# Devices.net
KiCad netlist of a schematic drawn in Altium Designer
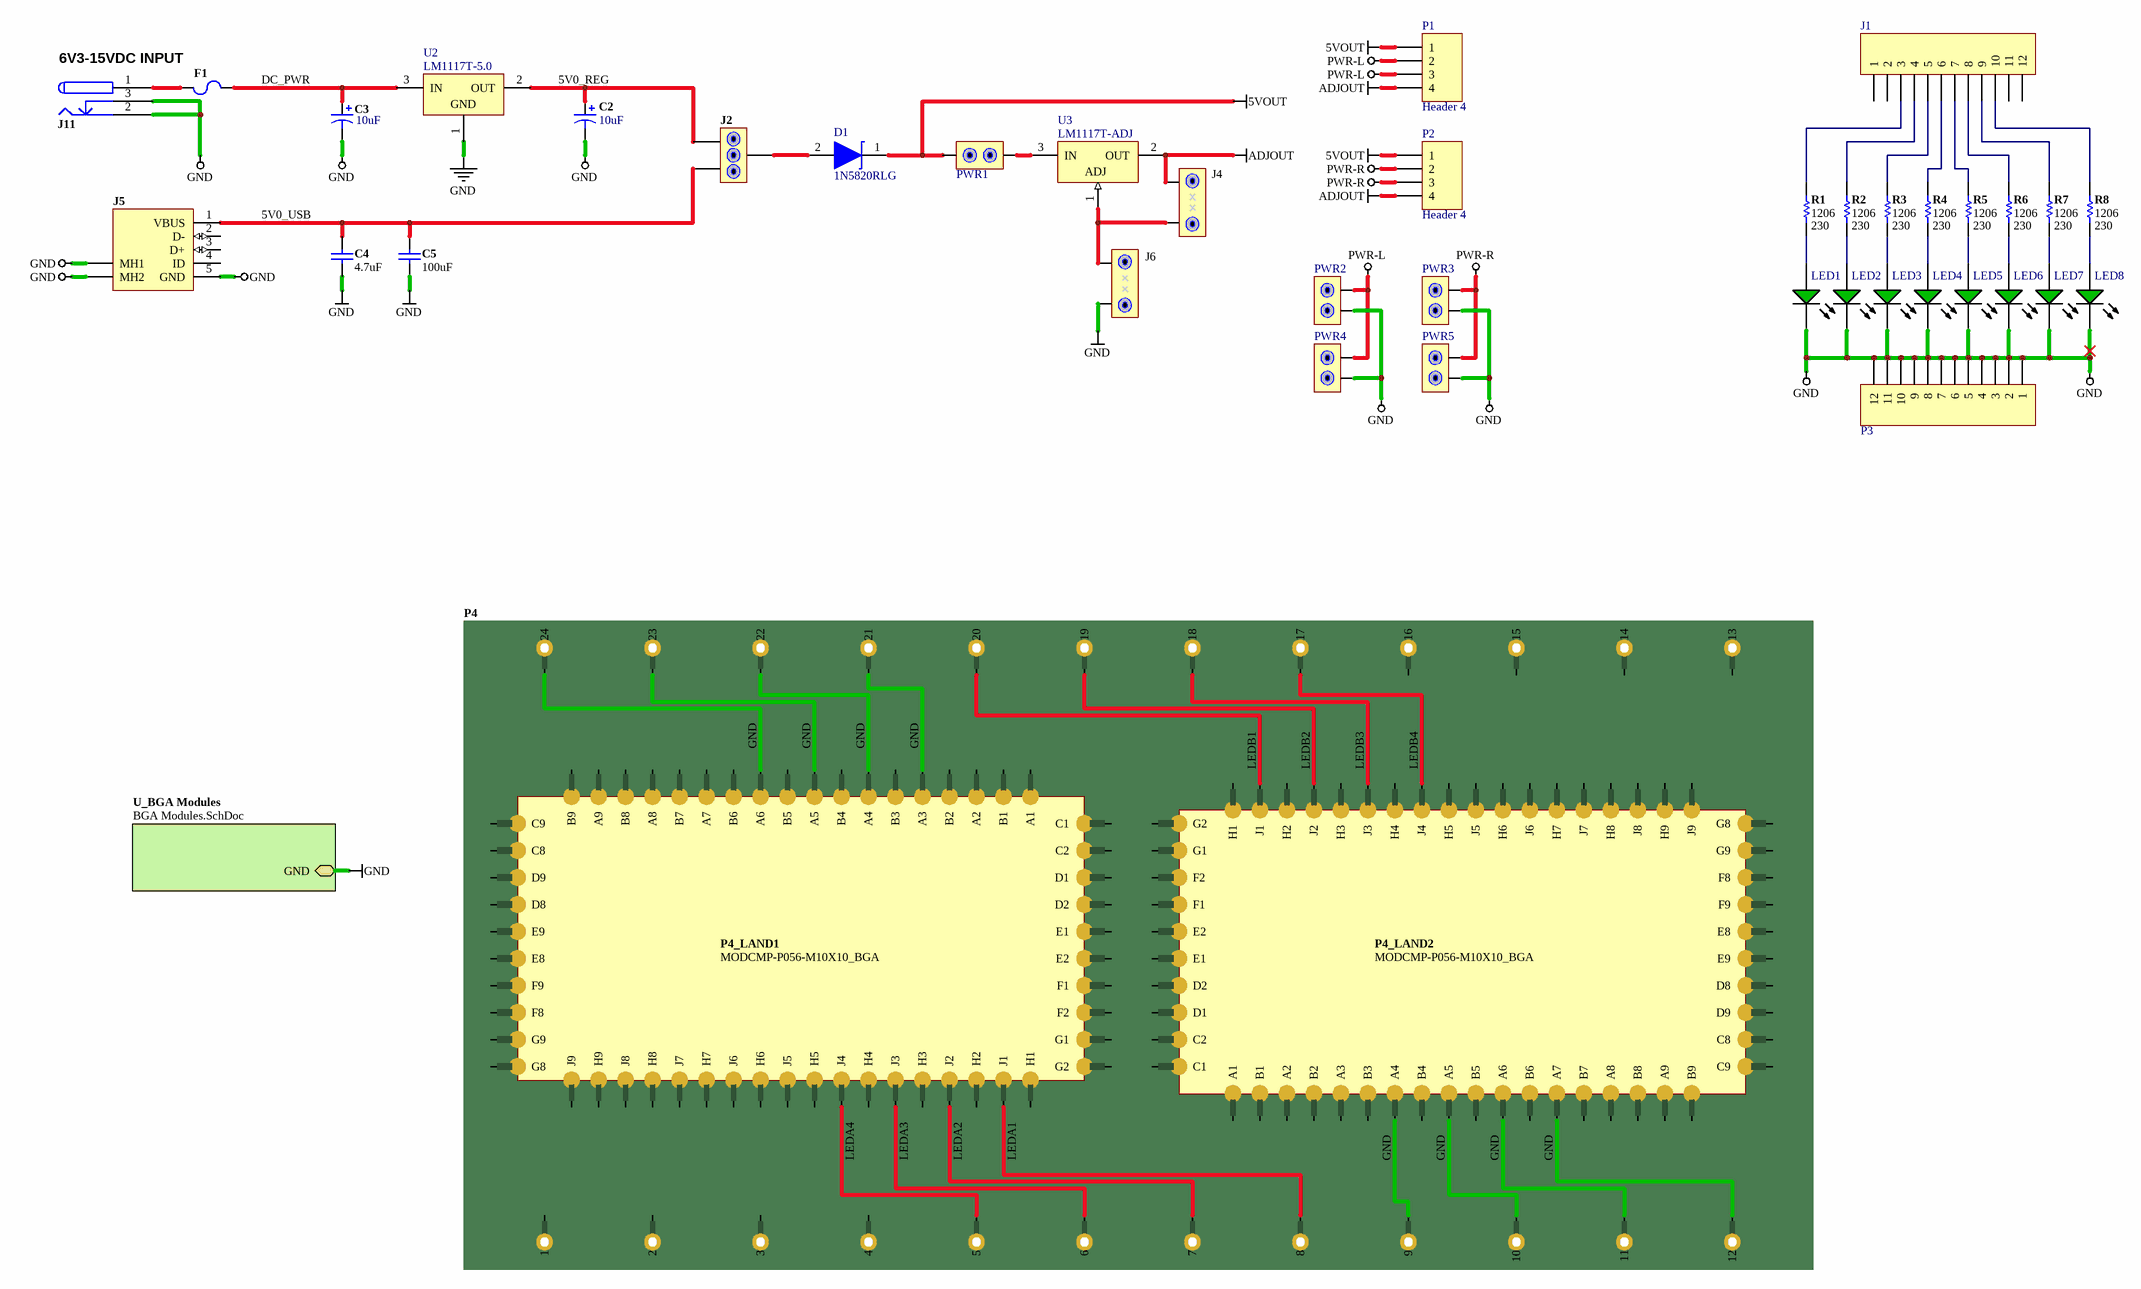
[diagram p0: Devices.SchDoc]

(export (version "E")
  (design (tool "Eeschema 10.0.6"))
  (components
    (comp (ref "C2")
      (value "TAJB106K020R")
      (footprint "AVX-CAPC3528_V")
      (description "Capacitor, Tantalum, 10uF 10% 20V MCCT-B (3528)")
      (fields
        (field (name "CAPACITANCE") "10uF")
        (field (name "MANUFACTURER") "AVX")
        (field (name "TOLERANCE") "10%")
      )
      (libsource (lib "Altium Content Vault") (part "CMP-0279-00001-1"))
    )
    (comp (ref "C3")
      (value "TAJB106K020R")
      (footprint "AVX-CAPC3528_V")
      (description "Capacitor, Tantalum, 10uF 10% 20V MCCT-B (3528)")
      (fields
        (field (name "CAPACITANCE") "10uF")
        (field (name "MANUFACTURER") "AVX")
        (field (name "TOLERANCE") "10%")
      )
      (libsource (lib "Altium Content Vault") (part "CMP-0279-00001-1"))
    )
    (comp (ref "C4")
      (value "4.7uF")
      (footprint "CAPC1206(3216)190_L")
      (description "CAP 100uF 6.3V ?0% 1206 (3216 Metric) Thickness 1.9mm SMD")
      (fields (field (name "TOLERANCE") "?0%") (field (name "Comment") "AP 4.7uF 6.3V 1206(3216)"))
      (libsource (lib "Component_DB") (part "CAP_NP"))
    )
    (comp (ref "C5")
      (value "100uF")
      (footprint "CAPC1206(3216)190_L")
      (description "CAP 100uF 6.3V ?0% 1206 (3216 Metric) Thickness 1.9mm SMD")
      (fields (field (name "TOLERANCE") "?0%") (field (name "Comment") "AP 100uF 6.3V 1206(3216)"))
      (libsource (lib "Component_DB") (part "CAP_NP"))
    )
    (comp (ref "D1")
      (value "1N5820RLG")
      (footprint "ONSC-AXIAL_LEAD-2-267-05_V")
      (description "Rectifier, 2-Pin Axial_Lead, Pb-Free, Tape and Reel")
      (fields (field (name "MANUFACTURER") "On Semiconductor"))
      (libsource (lib "Soldering_Trainer_Prj (backup)") (part "CMP-1055-00027-1"))
    )
    (comp (ref "F1")
      (value "SMD2920P300TF")
      (footprint "FUSE2920")
      (description "PTC RESETTABLE 16V 3A SMD 2920")
      (libsource (lib "Component_DB") (part "FUSE-2"))
    )
    (comp (ref "J1")
      (value "Header 12")
      (footprint "HDR1X12")
      (description "Header, 12-Pin")
      (fields (field (name "PUBLISHER") "Altium Limited"))
      (libsource (lib "") (part "Header 12_1"))
    )
    (comp (ref "J2")
      (value "3-WAY JUMPER")
      (footprint "HDR1X3")
      (description "3-Way Jumper - Center Output")
      (fields (field (name "MANUFACTURER PART NUMBER") "71417-103HLF"))
      (libsource (lib "3-WAY JUMPER") (part "3-WAY JUMPER"))
    )
    (comp (ref "J4")
      (value "801-87-004-10-001101")
      (footprint "HDR1X4")
      (description "IC REG LDO 3V3 .3A SOT25")
      (fields (field (name "DIGIKEY PART NUMBER") "1212-1181-ND"))
      (libsource (lib "801-87-004-10-001101 Socket") (part "801-87-004-10-001101"))
    )
    (comp (ref "J5")
      (value "UX60SC-MB-5S8")
      (footprint "UX60SC-MB-5S8")
      (description "CONN RCPT MINI USB2.0 5POS SLD")
      (libsource (lib "Component_DB") (part "UX60SC-MB-5S8"))
    )
    (comp (ref "J6")
      (value "801-87-004-10-001101")
      (footprint "HDR1X4")
      (description "IC REG LDO 3V3 .3A SOT25")
      (fields (field (name "DIGIKEY PART NUMBER") "1212-1181-ND"))
      (libsource (lib "801-87-004-10-001101 Socket") (part "801-87-004-10-001101"))
    )
    (comp (ref "J11")
      (value "PWR CONNECTOR")
      (footprint "PJ-102AH")
      (description "Connector, 3 Conductor Power Jack")
      (fields (field (name "MANUFACTURER PART NUMBER") "CP-102AH-ND"))
      (libsource (lib "PWR_CONNECTOR_3") (part "POWER-CONNECTOR-3"))
    )
    (comp (ref "LED1")
      (value "LED_1206")
      (footprint "RESC1206(3216)75_L")
      (description "GREEN color, 1206, SMD")
      (libsource (lib "Component_DB") (part "LED_GREEN_A1K2-2.A1"))
    )
    (comp (ref "LED2")
      (value "LED_1206")
      (footprint "RESC1206(3216)75_L")
      (description "GREEN color, 1206, SMD")
      (libsource (lib "Component_DB") (part "LED_GREEN_A1K2-2.A1"))
    )
    (comp (ref "LED3")
      (value "LED_1206")
      (footprint "RESC1206(3216)75_L")
      (description "GREEN color, 1206, SMD")
      (libsource (lib "Component_DB") (part "LED_GREEN_A1K2-2.A1"))
    )
    (comp (ref "LED4")
      (value "LED_1206")
      (footprint "RESC1206(3216)75_L")
      (description "GREEN color, 1206, SMD")
      (libsource (lib "Component_DB") (part "LED_GREEN_A1K2-2.A1"))
    )
    (comp (ref "LED5")
      (value "LED_1206")
      (footprint "RESC1206(3216)75_L")
      (description "GREEN color, 1206, SMD")
      (libsource (lib "Component_DB") (part "LED_GREEN_A1K2-2.A1"))
    )
    (comp (ref "LED6")
      (value "LED_1206")
      (footprint "RESC1206(3216)75_L")
      (description "GREEN color, 1206, SMD")
      (libsource (lib "Component_DB") (part "LED_GREEN_A1K2-2.A1"))
    )
    (comp (ref "LED7")
      (value "LED_1206")
      (footprint "RESC1206(3216)75_L")
      (description "GREEN color, 1206, SMD")
      (libsource (lib "Component_DB") (part "LED_GREEN_A1K2-2.A1"))
    )
    (comp (ref "LED8")
      (value "LED_1206")
      (footprint "RESC1206(3216)75_L")
      (description "GREEN color, 1206, SMD")
      (libsource (lib "Component_DB") (part "LED_GREEN_A1K2-2.A1"))
    )
    (comp (ref "P1")
      (value "Header 4")
      (footprint "HDR1X4")
      (description "Header, 4-Pin")
      (fields (field (name "PUBLISHER") "Altium Limited"))
      (libsource (lib "Miscellaneous Connectors") (part "Header 4"))
    )
    (comp (ref "P2")
      (value "Header 4")
      (footprint "HDR1X4")
      (description "Header, 4-Pin")
      (fields (field (name "PUBLISHER") "Altium Limited"))
      (libsource (lib "Miscellaneous Connectors") (part "Header 4"))
    )
    (comp (ref "P3")
      (value "Header 12")
      (footprint "HDR1X12")
      (description "Header, 12-Pin")
      (fields (field (name "PUBLISHER") "Altium Limited"))
      (libsource (lib "Miscellaneous Connectors") (part "Header 12"))
    )
    (comp (ref "P4")
      (value "BBCMP-P24-M1200X700")
      (footprint "BBCMP-P24-M1200X700")
      (libsource (lib "MODCMP-P056-M10X10_BGA") (part "BBCMP-P24"))
    )
    (comp (ref "P4_LAND1")
      (value "MODCMP-P056-M10X10_BGA")
      (footprint "MB2100.01.A.2")
      (description "Module Component - 1mm Pitch, 56-Pin, 10mmX10mm")
      (libsource (lib "MODCMP-P056-M10X10_BGA") (part "MODCMP-P056-M10X10_BGA"))
    )
    (comp (ref "P4_LAND2")
      (value "MODCMP-P056-M10X10_BGA")
      (footprint "MB2100.01.A.2")
      (description "Module Component - 1mm Pitch, 56-Pin, 10mmX10mm")
      (libsource (lib "MODCMP-P056-M10X10_BGA") (part "MODCMP-P056-M10X10_BGA"))
    )
    (comp (ref "PWR1")
      (value "Jumper")
      (footprint "JMP1X2")
      (description "Standard 2 Pin Jumper, 100mil spacing")
      (fields (field (name "MANUFACTURER PART NUMBER") "M20-9770246"))
      (libsource (lib "Soldering_Trainer_Prj") (part "JMP1X2_SERIES"))
    )
    (comp (ref "PWR2")
      (value "Jumper")
      (footprint "JMP1X2")
      (description "Standard 2 Pin Jumper, 100mil spacing")
      (fields (field (name "MANUFACTURER PART NUMBER") "M20-9770246"))
      (libsource (lib "JMP1X2") (part "JMP1X2"))
    )
    (comp (ref "PWR3")
      (value "Jumper")
      (footprint "JMP1X2")
      (description "Standard 2 Pin Jumper, 100mil spacing")
      (fields (field (name "MANUFACTURER PART NUMBER") "M20-9770246"))
      (libsource (lib "JMP1X2") (part "JMP1X2"))
    )
    (comp (ref "PWR4")
      (value "Jumper")
      (footprint "JMP1X2")
      (description "Standard 2 Pin Jumper, 100mil spacing")
      (fields (field (name "MANUFACTURER PART NUMBER") "M20-9770246"))
      (libsource (lib "JMP1X2") (part "JMP1X2"))
    )
    (comp (ref "PWR5")
      (value "Jumper")
      (footprint "JMP1X2")
      (description "Standard 2 Pin Jumper, 100mil spacing")
      (fields (field (name "MANUFACTURER PART NUMBER") "M20-9770246"))
      (libsource (lib "JMP1X2") (part "JMP1X2"))
    )
    (comp (ref "R1")
      (value "1206")
      (footprint "RESC1206(3216)75_L")
      (description "Jumper 0805 (2012 Metric)")
      (fields (field (name "VALUE (OHMS)") "230") (field (name "POWER") "None"))
      (libsource (lib "Component_DB") (part "RES"))
    )
    (comp (ref "R2")
      (value "1206")
      (footprint "RESC1206(3216)75_L")
      (description "Jumper 0805 (2012 Metric)")
      (fields (field (name "VALUE (OHMS)") "230") (field (name "POWER") "None"))
      (libsource (lib "Component_DB") (part "RES"))
    )
    (comp (ref "R3")
      (value "1206")
      (footprint "RESC1206(3216)75_L")
      (description "Jumper 0805 (2012 Metric)")
      (fields (field (name "VALUE (OHMS)") "230") (field (name "POWER") "None"))
      (libsource (lib "Component_DB") (part "RES"))
    )
    (comp (ref "R4")
      (value "1206")
      (footprint "RESC1206(3216)75_L")
      (description "Jumper 0805 (2012 Metric)")
      (fields (field (name "VALUE (OHMS)") "230") (field (name "POWER") "None"))
      (libsource (lib "Component_DB") (part "RES"))
    )
    (comp (ref "R5")
      (value "1206")
      (footprint "RESC1206(3216)75_L")
      (description "Jumper 0805 (2012 Metric)")
      (fields (field (name "VALUE (OHMS)") "230") (field (name "POWER") "None"))
      (libsource (lib "Component_DB") (part "RES"))
    )
    (comp (ref "R6")
      (value "1206")
      (footprint "RESC1206(3216)75_L")
      (description "Jumper 0805 (2012 Metric)")
      (fields (field (name "VALUE (OHMS)") "230") (field (name "POWER") "None"))
      (libsource (lib "Component_DB") (part "RES"))
    )
    (comp (ref "R7")
      (value "1206")
      (footprint "RESC1206(3216)75_L")
      (description "Jumper 0805 (2012 Metric)")
      (fields (field (name "VALUE (OHMS)") "230") (field (name "POWER") "None"))
      (libsource (lib "Component_DB") (part "RES"))
    )
    (comp (ref "R8")
      (value "1206")
      (footprint "RESC1206(3216)75_L")
      (description "Jumper 0805 (2012 Metric)")
      (fields (field (name "VALUE (OHMS)") "230") (field (name "POWER") "None"))
      (libsource (lib "Component_DB") (part "RES"))
    )
    (comp (ref "U2")
      (value "LM1117T-5.0")
      (footprint "T03B")
      (description "800mA Low-Dropout Linear Regulator, 3-pin TO-220")
      (fields (field (name "MANUFACTURER") "National Semiconductor"))
      (libsource (lib "Altium Content Vault") (part "PM-REG-LM1086-SIL3"))
    )
    (comp (ref "U3")
      (value "LM1117T-ADJ")
      (footprint "T03B")
      (description "800mA Low-Dropout Linear Regulator, 3-pin TO-220, Pb-Free")
      (fields (field (name "MANUFACTURER") "National Semiconductor"))
      (libsource (lib "Altium Content Vault") (part "CMP-0062-02492-2"))
    )
  )
  (nets
    (net (code "1") (name "/5V0_REG") (class "Default")
      (node (ref "C2") (pin "1") (pinfunction "1_1") (pintype "passive"))
      (node (ref "J2") (pin "1") (pinfunction "1_1") (pintype "passive"))
      (node (ref "U2") (pin "2") (pinfunction "OUT_2") (pintype "power_in"))
    )
    (net (code "2") (name "/5V0_USB") (class "Default")
      (node (ref "C4") (pin "1") (pinfunction "1_1") (pintype "passive"))
      (node (ref "C5") (pin "1") (pinfunction "1_1") (pintype "passive"))
      (node (ref "J2") (pin "3") (pinfunction "3_3") (pintype "passive"))
      (node (ref "J5") (pin "1") (pinfunction "VBUS_1") (pintype "power_in"))
    )
    (net (code "3") (name "/DC_PWR") (class "Default")
      (node (ref "C3") (pin "1") (pinfunction "1_1") (pintype "passive"))
      (node (ref "F1") (pin "1") (pinfunction "1_1") (pintype "passive"))
      (node (ref "U2") (pin "3") (pinfunction "IN_3") (pintype "power_in"))
    )
    (net (code "4") (name "/LEDA1") (class "Default")
      (node (ref "P4") (pin "8") (pinfunction "8_8") (pintype "passive"))
      (node (ref "P4_LAND1") (pin "J1") (pinfunction "J1_J1") (pintype "passive"))
    )
    (net (code "5") (name "/LEDA2") (class "Default")
      (node (ref "P4") (pin "7") (pinfunction "7_7") (pintype "passive"))
      (node (ref "P4_LAND1") (pin "J2") (pinfunction "J2_J2") (pintype "passive"))
    )
    (net (code "6") (name "/LEDA3") (class "Default")
      (node (ref "P4") (pin "6") (pinfunction "6_6") (pintype "passive"))
      (node (ref "P4_LAND1") (pin "J3") (pinfunction "J3_J3") (pintype "passive"))
    )
    (net (code "7") (name "/LEDA4") (class "Default")
      (node (ref "P4") (pin "5") (pinfunction "5_5") (pintype "passive"))
      (node (ref "P4_LAND1") (pin "J4") (pinfunction "J4_J4") (pintype "passive"))
    )
    (net (code "8") (name "/LEDB1") (class "Default")
      (node (ref "P4") (pin "20") (pinfunction "20_20") (pintype "passive"))
      (node (ref "P4_LAND2") (pin "J1") (pinfunction "J1_J1") (pintype "passive"))
    )
    (net (code "9") (name "/LEDB2") (class "Default")
      (node (ref "P4") (pin "19") (pinfunction "19_19") (pintype "passive"))
      (node (ref "P4_LAND2") (pin "J2") (pinfunction "J2_J2") (pintype "passive"))
    )
    (net (code "10") (name "/LEDB3") (class "Default")
      (node (ref "P4") (pin "18") (pinfunction "18_18") (pintype "passive"))
      (node (ref "P4_LAND2") (pin "J3") (pinfunction "J3_J3") (pintype "passive"))
    )
    (net (code "11") (name "/LEDB4") (class "Default")
      (node (ref "P4") (pin "17") (pinfunction "17_17") (pintype "passive"))
      (node (ref "P4_LAND2") (pin "J4") (pinfunction "J4_J4") (pintype "passive"))
    )
    (net (code "12") (name "5VOUT") (class "Default")
      (node (ref "D1") (pin "1") (pinfunction "K_1") (pintype "passive"))
      (node (ref "P1") (pin "1") (pinfunction "1_1") (pintype "passive"))
      (node (ref "P2") (pin "1") (pinfunction "1_1") (pintype "passive"))
      (node (ref "PWR1") (pin "1") (pinfunction "1_1") (pintype "passive"))
    )
    (net (code "13") (name "ADJOUT") (class "Default")
      (node (ref "J4") (pin "1") (pinfunction "1_1") (pintype "passive"))
      (node (ref "P1") (pin "4") (pinfunction "4_4") (pintype "passive"))
      (node (ref "P2") (pin "4") (pinfunction "4_4") (pintype "passive"))
      (node (ref "U3") (pin "2") (pinfunction "OUT_2") (pintype "power_in"))
    )
    (net (code "14") (name "GND") (class "Default")
      (node (ref "C2") (pin "2") (pinfunction "2_2") (pintype "passive"))
      (node (ref "C3") (pin "2") (pinfunction "2_2") (pintype "passive"))
      (node (ref "C4") (pin "2") (pinfunction "2_2") (pintype "passive"))
      (node (ref "C5") (pin "2") (pinfunction "2_2") (pintype "passive"))
      (node (ref "J11") (pin "2") (pintype "power_in"))
      (node (ref "J11") (pin "3") (pintype "power_in"))
      (node (ref "J5") (pin "5") (pinfunction "GND_5") (pintype "power_in"))
      (node (ref "J5") (pin "MH1") (pinfunction "MH1_MH1") (pintype "passive"))
      (node (ref "J5") (pin "MH2") (pinfunction "MH2_MH2") (pintype "passive"))
      (node (ref "J6") (pin "4") (pinfunction "4_4") (pintype "passive"))
      (node (ref "LED1") (pin "2") (pinfunction "K_2") (pintype "passive"))
      (node (ref "LED2") (pin "2") (pinfunction "K_2") (pintype "passive"))
      (node (ref "LED3") (pin "2") (pinfunction "K_2") (pintype "passive"))
      (node (ref "LED4") (pin "2") (pinfunction "K_2") (pintype "passive"))
      (node (ref "LED5") (pin "2") (pinfunction "K_2") (pintype "passive"))
      (node (ref "LED6") (pin "2") (pinfunction "K_2") (pintype "passive"))
      (node (ref "LED7") (pin "2") (pinfunction "K_2") (pintype "passive"))
      (node (ref "LED8") (pin "2") (pinfunction "K_2") (pintype "passive"))
      (node (ref "P3") (pin "1") (pinfunction "1_1") (pintype "passive"))
      (node (ref "P3") (pin "10") (pinfunction "10_10") (pintype "passive"))
      (node (ref "P3") (pin "11") (pinfunction "11_11") (pintype "passive"))
      (node (ref "P3") (pin "12") (pinfunction "12_12") (pintype "passive"))
      (node (ref "P3") (pin "2") (pinfunction "2_2") (pintype "passive"))
      (node (ref "P3") (pin "3") (pinfunction "3_3") (pintype "passive"))
      (node (ref "P3") (pin "4") (pinfunction "4_4") (pintype "passive"))
      (node (ref "P3") (pin "5") (pinfunction "5_5") (pintype "passive"))
      (node (ref "P3") (pin "6") (pinfunction "6_6") (pintype "passive"))
      (node (ref "P3") (pin "7") (pinfunction "7_7") (pintype "passive"))
      (node (ref "P3") (pin "8") (pinfunction "8_8") (pintype "passive"))
      (node (ref "P3") (pin "9") (pinfunction "9_9") (pintype "passive"))
      (node (ref "P4") (pin "10") (pinfunction "10_10") (pintype "passive"))
      (node (ref "P4") (pin "11") (pinfunction "11_11") (pintype "passive"))
      (node (ref "P4") (pin "12") (pinfunction "12_12") (pintype "passive"))
      (node (ref "P4") (pin "21") (pinfunction "21_21") (pintype "passive"))
      (node (ref "P4") (pin "22") (pinfunction "22_22") (pintype "passive"))
      (node (ref "P4") (pin "23") (pinfunction "23_23") (pintype "passive"))
      (node (ref "P4") (pin "24") (pinfunction "24_24") (pintype "passive"))
      (node (ref "P4") (pin "9") (pinfunction "9_9") (pintype "passive"))
      (node (ref "P4_LAND1") (pin "A3") (pinfunction "A3_A3") (pintype "passive"))
      (node (ref "P4_LAND1") (pin "A4") (pinfunction "A4_A4") (pintype "passive"))
      (node (ref "P4_LAND1") (pin "A5") (pinfunction "A5_A5") (pintype "passive"))
      (node (ref "P4_LAND1") (pin "A6") (pinfunction "A6_A6") (pintype "passive"))
      (node (ref "P4_LAND2") (pin "A4") (pinfunction "A4_A4") (pintype "passive"))
      (node (ref "P4_LAND2") (pin "A5") (pinfunction "A5_A5") (pintype "passive"))
      (node (ref "P4_LAND2") (pin "A6") (pinfunction "A6_A6") (pintype "passive"))
      (node (ref "P4_LAND2") (pin "A7") (pinfunction "A7_A7") (pintype "passive"))
      (node (ref "PWR2") (pin "1") (pinfunction "1_1") (pintype "passive"))
      (node (ref "PWR3") (pin "1") (pinfunction "1_1") (pintype "passive"))
      (node (ref "PWR4") (pin "1") (pinfunction "1_1") (pintype "passive"))
      (node (ref "PWR5") (pin "1") (pinfunction "1_1") (pintype "passive"))
      (node (ref "U2") (pin "1") (pinfunction "GND_1") (pintype "power_in"))
    )
    (net (code "15") (name "Net-(D1-A)") (class "Default")
      (node (ref "D1") (pin "2") (pinfunction "A_2") (pintype "passive"))
      (node (ref "J2") (pin "2") (pinfunction "2_2") (pintype "passive"))
    )
    (net (code "16") (name "Net-(F1-Pad2)") (class "Default")
      (node (ref "F1") (pin "2") (pinfunction "2_2") (pintype "passive"))
      (node (ref "J11") (pin "1") (pintype "power_in"))
    )
    (net (code "17") (name "Net-(J1-Pad3)") (class "Default")
      (node (ref "J1") (pin "3") (pinfunction "3_3") (pintype "passive"))
      (node (ref "R1") (pin "2") (pinfunction "2_2") (pintype "passive"))
    )
    (net (code "18") (name "Net-(J1-Pad4)") (class "Default")
      (node (ref "J1") (pin "4") (pinfunction "4_4") (pintype "passive"))
      (node (ref "R2") (pin "2") (pinfunction "2_2") (pintype "passive"))
    )
    (net (code "19") (name "Net-(J1-Pad5)") (class "Default")
      (node (ref "J1") (pin "5") (pinfunction "5_5") (pintype "passive"))
      (node (ref "R3") (pin "2") (pinfunction "2_2") (pintype "passive"))
    )
    (net (code "20") (name "Net-(J1-Pad6)") (class "Default")
      (node (ref "J1") (pin "6") (pinfunction "6_6") (pintype "passive"))
      (node (ref "R4") (pin "2") (pinfunction "2_2") (pintype "passive"))
    )
    (net (code "21") (name "Net-(J1-Pad7)") (class "Default")
      (node (ref "J1") (pin "7") (pinfunction "7_7") (pintype "passive"))
      (node (ref "R5") (pin "2") (pinfunction "2_2") (pintype "passive"))
    )
    (net (code "22") (name "Net-(J1-Pad8)") (class "Default")
      (node (ref "J1") (pin "8") (pinfunction "8_8") (pintype "passive"))
      (node (ref "R6") (pin "2") (pinfunction "2_2") (pintype "passive"))
    )
    (net (code "23") (name "Net-(J1-Pad9)") (class "Default")
      (node (ref "J1") (pin "9") (pinfunction "9_9") (pintype "passive"))
      (node (ref "R7") (pin "2") (pinfunction "2_2") (pintype "passive"))
    )
    (net (code "24") (name "Net-(J1-Pad10)") (class "Default")
      (node (ref "J1") (pin "10") (pinfunction "10_10") (pintype "passive"))
      (node (ref "R8") (pin "2") (pinfunction "2_2") (pintype "passive"))
    )
    (net (code "25") (name "Net-(LED1-A)") (class "Default")
      (node (ref "LED1") (pin "1") (pinfunction "A_1") (pintype "passive"))
      (node (ref "R1") (pin "1") (pinfunction "1_1") (pintype "passive"))
    )
    (net (code "26") (name "Net-(LED2-A)") (class "Default")
      (node (ref "LED2") (pin "1") (pinfunction "A_1") (pintype "passive"))
      (node (ref "R2") (pin "1") (pinfunction "1_1") (pintype "passive"))
    )
    (net (code "27") (name "Net-(LED3-A)") (class "Default")
      (node (ref "LED3") (pin "1") (pinfunction "A_1") (pintype "passive"))
      (node (ref "R3") (pin "1") (pinfunction "1_1") (pintype "passive"))
    )
    (net (code "28") (name "Net-(LED4-A)") (class "Default")
      (node (ref "LED4") (pin "1") (pinfunction "A_1") (pintype "passive"))
      (node (ref "R4") (pin "1") (pinfunction "1_1") (pintype "passive"))
    )
    (net (code "29") (name "Net-(LED5-A)") (class "Default")
      (node (ref "LED5") (pin "1") (pinfunction "A_1") (pintype "passive"))
      (node (ref "R5") (pin "1") (pinfunction "1_1") (pintype "passive"))
    )
    (net (code "30") (name "Net-(LED6-A)") (class "Default")
      (node (ref "LED6") (pin "1") (pinfunction "A_1") (pintype "passive"))
      (node (ref "R6") (pin "1") (pinfunction "1_1") (pintype "passive"))
    )
    (net (code "31") (name "Net-(LED7-A)") (class "Default")
      (node (ref "LED7") (pin "1") (pinfunction "A_1") (pintype "passive"))
      (node (ref "R7") (pin "1") (pinfunction "1_1") (pintype "passive"))
    )
    (net (code "32") (name "Net-(LED8-A)") (class "Default")
      (node (ref "LED8") (pin "1") (pinfunction "A_1") (pintype "passive"))
      (node (ref "R8") (pin "1") (pinfunction "1_1") (pintype "passive"))
    )
    (net (code "33") (name "Net-(U3-ADJ)") (class "Default")
      (node (ref "J4") (pin "4") (pinfunction "4_4") (pintype "passive"))
      (node (ref "J6") (pin "1") (pinfunction "1_1") (pintype "passive"))
      (node (ref "U3") (pin "1") (pinfunction "ADJ_1") (pintype "input"))
    )
    (net (code "34") (name "Net-(U3-IN)") (class "Default")
      (node (ref "PWR1") (pin "2") (pinfunction "2_2") (pintype "passive"))
      (node (ref "U3") (pin "3") (pinfunction "IN_3") (pintype "power_in"))
    )
    (net (code "35") (name "PWR-L") (class "Default")
      (node (ref "P1") (pin "2") (pinfunction "2_2") (pintype "passive"))
      (node (ref "P1") (pin "3") (pinfunction "3_3") (pintype "passive"))
      (node (ref "PWR2") (pin "2") (pinfunction "2_2") (pintype "passive"))
      (node (ref "PWR4") (pin "2") (pinfunction "2_2") (pintype "passive"))
    )
    (net (code "36") (name "PWR-R") (class "Default")
      (node (ref "P2") (pin "2") (pinfunction "2_2") (pintype "passive"))
      (node (ref "P2") (pin "3") (pinfunction "3_3") (pintype "passive"))
      (node (ref "PWR3") (pin "2") (pinfunction "2_2") (pintype "passive"))
      (node (ref "PWR5") (pin "2") (pinfunction "2_2") (pintype "passive"))
    )
    (net (code "37") (name "unconnected-(J1-Pad1)") (class "Default")
      (node (ref "J1") (pin "1") (pinfunction "1_1") (pintype "passive"))
    )
    (net (code "38") (name "unconnected-(J1-Pad2)") (class "Default")
      (node (ref "J1") (pin "2") (pinfunction "2_2") (pintype "passive"))
    )
    (net (code "39") (name "unconnected-(J1-Pad11)") (class "Default")
      (node (ref "J1") (pin "11") (pinfunction "11_11") (pintype "passive"))
    )
    (net (code "40") (name "unconnected-(J1-Pad12)") (class "Default")
      (node (ref "J1") (pin "12") (pinfunction "12_12") (pintype "passive"))
    )
    (net (code "41") (name "unconnected-(J5-D+-Pad3)") (class "Default")
      (node (ref "J5") (pin "3") (pinfunction "D+_3") (pintype "bidirectional"))
    )
    (net (code "42") (name "unconnected-(J5-D--Pad2)") (class "Default")
      (node (ref "J5") (pin "2") (pinfunction "D-_2") (pintype "bidirectional"))
    )
    (net (code "43") (name "unconnected-(J5-ID-Pad4)") (class "Default")
      (node (ref "J5") (pin "4") (pinfunction "ID_4") (pintype "passive"))
    )
    (net (code "44") (name "unconnected-(P4-Pad1)") (class "Default")
      (node (ref "P4") (pin "1") (pinfunction "1_1") (pintype "passive"))
    )
    (net (code "45") (name "unconnected-(P4-Pad2)") (class "Default")
      (node (ref "P4") (pin "2") (pinfunction "2_2") (pintype "passive"))
    )
    (net (code "46") (name "unconnected-(P4-Pad3)") (class "Default")
      (node (ref "P4") (pin "3") (pinfunction "3_3") (pintype "passive"))
    )
    (net (code "47") (name "unconnected-(P4-Pad4)") (class "Default")
      (node (ref "P4") (pin "4") (pinfunction "4_4") (pintype "passive"))
    )
    (net (code "48") (name "unconnected-(P4-Pad13)") (class "Default")
      (node (ref "P4") (pin "13") (pinfunction "13_13") (pintype "passive"))
    )
    (net (code "49") (name "unconnected-(P4-Pad14)") (class "Default")
      (node (ref "P4") (pin "14") (pinfunction "14_14") (pintype "passive"))
    )
    (net (code "50") (name "unconnected-(P4-Pad15)") (class "Default")
      (node (ref "P4") (pin "15") (pinfunction "15_15") (pintype "passive"))
    )
    (net (code "51") (name "unconnected-(P4-Pad16)") (class "Default")
      (node (ref "P4") (pin "16") (pinfunction "16_16") (pintype "passive"))
    )
    (net (code "52") (name "unconnected-(P4_LAND1-PadA1)") (class "Default")
      (node (ref "P4_LAND1") (pin "A1") (pinfunction "A1_A1") (pintype "passive"))
    )
    (net (code "53") (name "unconnected-(P4_LAND1-PadA2)") (class "Default")
      (node (ref "P4_LAND1") (pin "A2") (pinfunction "A2_A2") (pintype "passive"))
    )
    (net (code "54") (name "unconnected-(P4_LAND1-PadA7)") (class "Default")
      (node (ref "P4_LAND1") (pin "A7") (pinfunction "A7_A7") (pintype "passive"))
    )
    (net (code "55") (name "unconnected-(P4_LAND1-PadA8)") (class "Default")
      (node (ref "P4_LAND1") (pin "A8") (pinfunction "A8_A8") (pintype "passive"))
    )
    (net (code "56") (name "unconnected-(P4_LAND1-PadA9)") (class "Default")
      (node (ref "P4_LAND1") (pin "A9") (pinfunction "A9_A9") (pintype "passive"))
    )
    (net (code "57") (name "unconnected-(P4_LAND1-PadB1)") (class "Default")
      (node (ref "P4_LAND1") (pin "B1") (pinfunction "B1_B1") (pintype "passive"))
    )
    (net (code "58") (name "unconnected-(P4_LAND1-PadB2)") (class "Default")
      (node (ref "P4_LAND1") (pin "B2") (pinfunction "B2_B2") (pintype "passive"))
    )
    (net (code "59") (name "unconnected-(P4_LAND1-PadB3)") (class "Default")
      (node (ref "P4_LAND1") (pin "B3") (pinfunction "B3_B3") (pintype "passive"))
    )
    (net (code "60") (name "unconnected-(P4_LAND1-PadB4)") (class "Default")
      (node (ref "P4_LAND1") (pin "B4") (pinfunction "B4_B4") (pintype "passive"))
    )
    (net (code "61") (name "unconnected-(P4_LAND1-PadB5)") (class "Default")
      (node (ref "P4_LAND1") (pin "B5") (pinfunction "B5_B5") (pintype "passive"))
    )
    (net (code "62") (name "unconnected-(P4_LAND1-PadB6)") (class "Default")
      (node (ref "P4_LAND1") (pin "B6") (pinfunction "B6_B6") (pintype "passive"))
    )
    (net (code "63") (name "unconnected-(P4_LAND1-PadB7)") (class "Default")
      (node (ref "P4_LAND1") (pin "B7") (pinfunction "B7_B7") (pintype "passive"))
    )
    (net (code "64") (name "unconnected-(P4_LAND1-PadB8)") (class "Default")
      (node (ref "P4_LAND1") (pin "B8") (pinfunction "B8_B8") (pintype "passive"))
    )
    (net (code "65") (name "unconnected-(P4_LAND1-PadB9)") (class "Default")
      (node (ref "P4_LAND1") (pin "B9") (pinfunction "B9_B9") (pintype "passive"))
    )
    (net (code "66") (name "unconnected-(P4_LAND1-PadC1)") (class "Default")
      (node (ref "P4_LAND1") (pin "C1") (pinfunction "C1_C1") (pintype "passive"))
    )
    (net (code "67") (name "unconnected-(P4_LAND1-PadC2)") (class "Default")
      (node (ref "P4_LAND1") (pin "C2") (pinfunction "C2_C2") (pintype "passive"))
    )
    (net (code "68") (name "unconnected-(P4_LAND1-PadC8)") (class "Default")
      (node (ref "P4_LAND1") (pin "C8") (pinfunction "C8_C8") (pintype "passive"))
    )
    (net (code "69") (name "unconnected-(P4_LAND1-PadC9)") (class "Default")
      (node (ref "P4_LAND1") (pin "C9") (pinfunction "C9_C9") (pintype "passive"))
    )
    (net (code "70") (name "unconnected-(P4_LAND1-PadD1)") (class "Default")
      (node (ref "P4_LAND1") (pin "D1") (pinfunction "D1_D1") (pintype "passive"))
    )
    (net (code "71") (name "unconnected-(P4_LAND1-PadD2)") (class "Default")
      (node (ref "P4_LAND1") (pin "D2") (pinfunction "D2_D2") (pintype "passive"))
    )
    (net (code "72") (name "unconnected-(P4_LAND1-PadD8)") (class "Default")
      (node (ref "P4_LAND1") (pin "D8") (pinfunction "D8_D8") (pintype "passive"))
    )
    (net (code "73") (name "unconnected-(P4_LAND1-PadD9)") (class "Default")
      (node (ref "P4_LAND1") (pin "D9") (pinfunction "D9_D9") (pintype "passive"))
    )
    (net (code "74") (name "unconnected-(P4_LAND1-PadE1)") (class "Default")
      (node (ref "P4_LAND1") (pin "E1") (pinfunction "E1_E1") (pintype "passive"))
    )
    (net (code "75") (name "unconnected-(P4_LAND1-PadE2)") (class "Default")
      (node (ref "P4_LAND1") (pin "E2") (pinfunction "E2_E2") (pintype "passive"))
    )
    (net (code "76") (name "unconnected-(P4_LAND1-PadE8)") (class "Default")
      (node (ref "P4_LAND1") (pin "E8") (pinfunction "E8_E8") (pintype "passive"))
    )
    (net (code "77") (name "unconnected-(P4_LAND1-PadE9)") (class "Default")
      (node (ref "P4_LAND1") (pin "E9") (pinfunction "E9_E9") (pintype "passive"))
    )
    (net (code "78") (name "unconnected-(P4_LAND1-PadF1)") (class "Default")
      (node (ref "P4_LAND1") (pin "F1") (pinfunction "F1_F1") (pintype "passive"))
    )
    (net (code "79") (name "unconnected-(P4_LAND1-PadF2)") (class "Default")
      (node (ref "P4_LAND1") (pin "F2") (pinfunction "F2_F2") (pintype "passive"))
    )
    (net (code "80") (name "unconnected-(P4_LAND1-PadF8)") (class "Default")
      (node (ref "P4_LAND1") (pin "F8") (pinfunction "F8_F8") (pintype "passive"))
    )
    (net (code "81") (name "unconnected-(P4_LAND1-PadF9)") (class "Default")
      (node (ref "P4_LAND1") (pin "F9") (pinfunction "F9_F9") (pintype "passive"))
    )
    (net (code "82") (name "unconnected-(P4_LAND1-PadG1)") (class "Default")
      (node (ref "P4_LAND1") (pin "G1") (pinfunction "G1_G1") (pintype "passive"))
    )
    (net (code "83") (name "unconnected-(P4_LAND1-PadG2)") (class "Default")
      (node (ref "P4_LAND1") (pin "G2") (pinfunction "G2_G2") (pintype "passive"))
    )
    (net (code "84") (name "unconnected-(P4_LAND1-PadG8)") (class "Default")
      (node (ref "P4_LAND1") (pin "G8") (pinfunction "G8_G8") (pintype "passive"))
    )
    (net (code "85") (name "unconnected-(P4_LAND1-PadG9)") (class "Default")
      (node (ref "P4_LAND1") (pin "G9") (pinfunction "G9_G9") (pintype "passive"))
    )
    (net (code "86") (name "unconnected-(P4_LAND1-PadH1)") (class "Default")
      (node (ref "P4_LAND1") (pin "H1") (pinfunction "H1_H1") (pintype "passive"))
    )
    (net (code "87") (name "unconnected-(P4_LAND1-PadH2)") (class "Default")
      (node (ref "P4_LAND1") (pin "H2") (pinfunction "H2_H2") (pintype "passive"))
    )
    (net (code "88") (name "unconnected-(P4_LAND1-PadH3)") (class "Default")
      (node (ref "P4_LAND1") (pin "H3") (pinfunction "H3_H3") (pintype "passive"))
    )
    (net (code "89") (name "unconnected-(P4_LAND1-PadH4)") (class "Default")
      (node (ref "P4_LAND1") (pin "H4") (pinfunction "H4_H4") (pintype "passive"))
    )
    (net (code "90") (name "unconnected-(P4_LAND1-PadH5)") (class "Default")
      (node (ref "P4_LAND1") (pin "H5") (pinfunction "H5_H5") (pintype "passive"))
    )
    (net (code "91") (name "unconnected-(P4_LAND1-PadH6)") (class "Default")
      (node (ref "P4_LAND1") (pin "H6") (pinfunction "H6_H6") (pintype "passive"))
    )
    (net (code "92") (name "unconnected-(P4_LAND1-PadH7)") (class "Default")
      (node (ref "P4_LAND1") (pin "H7") (pinfunction "H7_H7") (pintype "passive"))
    )
    (net (code "93") (name "unconnected-(P4_LAND1-PadH8)") (class "Default")
      (node (ref "P4_LAND1") (pin "H8") (pinfunction "H8_H8") (pintype "passive"))
    )
    (net (code "94") (name "unconnected-(P4_LAND1-PadH9)") (class "Default")
      (node (ref "P4_LAND1") (pin "H9") (pinfunction "H9_H9") (pintype "passive"))
    )
    (net (code "95") (name "unconnected-(P4_LAND1-PadJ5)") (class "Default")
      (node (ref "P4_LAND1") (pin "J5") (pinfunction "J5_J5") (pintype "passive"))
    )
    (net (code "96") (name "unconnected-(P4_LAND1-PadJ6)") (class "Default")
      (node (ref "P4_LAND1") (pin "J6") (pinfunction "J6_J6") (pintype "passive"))
    )
    (net (code "97") (name "unconnected-(P4_LAND1-PadJ7)") (class "Default")
      (node (ref "P4_LAND1") (pin "J7") (pinfunction "J7_J7") (pintype "passive"))
    )
    (net (code "98") (name "unconnected-(P4_LAND1-PadJ8)") (class "Default")
      (node (ref "P4_LAND1") (pin "J8") (pinfunction "J8_J8") (pintype "passive"))
    )
    (net (code "99") (name "unconnected-(P4_LAND1-PadJ9)") (class "Default")
      (node (ref "P4_LAND1") (pin "J9") (pinfunction "J9_J9") (pintype "passive"))
    )
    (net (code "100") (name "unconnected-(P4_LAND2-PadA1)") (class "Default")
      (node (ref "P4_LAND2") (pin "A1") (pinfunction "A1_A1") (pintype "passive"))
    )
    (net (code "101") (name "unconnected-(P4_LAND2-PadA2)") (class "Default")
      (node (ref "P4_LAND2") (pin "A2") (pinfunction "A2_A2") (pintype "passive"))
    )
    (net (code "102") (name "unconnected-(P4_LAND2-PadA3)") (class "Default")
      (node (ref "P4_LAND2") (pin "A3") (pinfunction "A3_A3") (pintype "passive"))
    )
    (net (code "103") (name "unconnected-(P4_LAND2-PadA8)") (class "Default")
      (node (ref "P4_LAND2") (pin "A8") (pinfunction "A8_A8") (pintype "passive"))
    )
    (net (code "104") (name "unconnected-(P4_LAND2-PadA9)") (class "Default")
      (node (ref "P4_LAND2") (pin "A9") (pinfunction "A9_A9") (pintype "passive"))
    )
    (net (code "105") (name "unconnected-(P4_LAND2-PadB1)") (class "Default")
      (node (ref "P4_LAND2") (pin "B1") (pinfunction "B1_B1") (pintype "passive"))
    )
    (net (code "106") (name "unconnected-(P4_LAND2-PadB2)") (class "Default")
      (node (ref "P4_LAND2") (pin "B2") (pinfunction "B2_B2") (pintype "passive"))
    )
    (net (code "107") (name "unconnected-(P4_LAND2-PadB3)") (class "Default")
      (node (ref "P4_LAND2") (pin "B3") (pinfunction "B3_B3") (pintype "passive"))
    )
    (net (code "108") (name "unconnected-(P4_LAND2-PadB4)") (class "Default")
      (node (ref "P4_LAND2") (pin "B4") (pinfunction "B4_B4") (pintype "passive"))
    )
    (net (code "109") (name "unconnected-(P4_LAND2-PadB5)") (class "Default")
      (node (ref "P4_LAND2") (pin "B5") (pinfunction "B5_B5") (pintype "passive"))
    )
    (net (code "110") (name "unconnected-(P4_LAND2-PadB6)") (class "Default")
      (node (ref "P4_LAND2") (pin "B6") (pinfunction "B6_B6") (pintype "passive"))
    )
    (net (code "111") (name "unconnected-(P4_LAND2-PadB7)") (class "Default")
      (node (ref "P4_LAND2") (pin "B7") (pinfunction "B7_B7") (pintype "passive"))
    )
    (net (code "112") (name "unconnected-(P4_LAND2-PadB8)") (class "Default")
      (node (ref "P4_LAND2") (pin "B8") (pinfunction "B8_B8") (pintype "passive"))
    )
    (net (code "113") (name "unconnected-(P4_LAND2-PadB9)") (class "Default")
      (node (ref "P4_LAND2") (pin "B9") (pinfunction "B9_B9") (pintype "passive"))
    )
    (net (code "114") (name "unconnected-(P4_LAND2-PadC1)") (class "Default")
      (node (ref "P4_LAND2") (pin "C1") (pinfunction "C1_C1") (pintype "passive"))
    )
    (net (code "115") (name "unconnected-(P4_LAND2-PadC2)") (class "Default")
      (node (ref "P4_LAND2") (pin "C2") (pinfunction "C2_C2") (pintype "passive"))
    )
    (net (code "116") (name "unconnected-(P4_LAND2-PadC8)") (class "Default")
      (node (ref "P4_LAND2") (pin "C8") (pinfunction "C8_C8") (pintype "passive"))
    )
    (net (code "117") (name "unconnected-(P4_LAND2-PadC9)") (class "Default")
      (node (ref "P4_LAND2") (pin "C9") (pinfunction "C9_C9") (pintype "passive"))
    )
    (net (code "118") (name "unconnected-(P4_LAND2-PadD1)") (class "Default")
      (node (ref "P4_LAND2") (pin "D1") (pinfunction "D1_D1") (pintype "passive"))
    )
    (net (code "119") (name "unconnected-(P4_LAND2-PadD2)") (class "Default")
      (node (ref "P4_LAND2") (pin "D2") (pinfunction "D2_D2") (pintype "passive"))
    )
    (net (code "120") (name "unconnected-(P4_LAND2-PadD8)") (class "Default")
      (node (ref "P4_LAND2") (pin "D8") (pinfunction "D8_D8") (pintype "passive"))
    )
    (net (code "121") (name "unconnected-(P4_LAND2-PadD9)") (class "Default")
      (node (ref "P4_LAND2") (pin "D9") (pinfunction "D9_D9") (pintype "passive"))
    )
    (net (code "122") (name "unconnected-(P4_LAND2-PadE1)") (class "Default")
      (node (ref "P4_LAND2") (pin "E1") (pinfunction "E1_E1") (pintype "passive"))
    )
    (net (code "123") (name "unconnected-(P4_LAND2-PadE2)") (class "Default")
      (node (ref "P4_LAND2") (pin "E2") (pinfunction "E2_E2") (pintype "passive"))
    )
    (net (code "124") (name "unconnected-(P4_LAND2-PadE8)") (class "Default")
      (node (ref "P4_LAND2") (pin "E8") (pinfunction "E8_E8") (pintype "passive"))
    )
    (net (code "125") (name "unconnected-(P4_LAND2-PadE9)") (class "Default")
      (node (ref "P4_LAND2") (pin "E9") (pinfunction "E9_E9") (pintype "passive"))
    )
    (net (code "126") (name "unconnected-(P4_LAND2-PadF1)") (class "Default")
      (node (ref "P4_LAND2") (pin "F1") (pinfunction "F1_F1") (pintype "passive"))
    )
    (net (code "127") (name "unconnected-(P4_LAND2-PadF2)") (class "Default")
      (node (ref "P4_LAND2") (pin "F2") (pinfunction "F2_F2") (pintype "passive"))
    )
    (net (code "128") (name "unconnected-(P4_LAND2-PadF8)") (class "Default")
      (node (ref "P4_LAND2") (pin "F8") (pinfunction "F8_F8") (pintype "passive"))
    )
    (net (code "129") (name "unconnected-(P4_LAND2-PadF9)") (class "Default")
      (node (ref "P4_LAND2") (pin "F9") (pinfunction "F9_F9") (pintype "passive"))
    )
    (net (code "130") (name "unconnected-(P4_LAND2-PadG1)") (class "Default")
      (node (ref "P4_LAND2") (pin "G1") (pinfunction "G1_G1") (pintype "passive"))
    )
    (net (code "131") (name "unconnected-(P4_LAND2-PadG2)") (class "Default")
      (node (ref "P4_LAND2") (pin "G2") (pinfunction "G2_G2") (pintype "passive"))
    )
    (net (code "132") (name "unconnected-(P4_LAND2-PadG8)") (class "Default")
      (node (ref "P4_LAND2") (pin "G8") (pinfunction "G8_G8") (pintype "passive"))
    )
    (net (code "133") (name "unconnected-(P4_LAND2-PadG9)") (class "Default")
      (node (ref "P4_LAND2") (pin "G9") (pinfunction "G9_G9") (pintype "passive"))
    )
    (net (code "134") (name "unconnected-(P4_LAND2-PadH1)") (class "Default")
      (node (ref "P4_LAND2") (pin "H1") (pinfunction "H1_H1") (pintype "passive"))
    )
    (net (code "135") (name "unconnected-(P4_LAND2-PadH2)") (class "Default")
      (node (ref "P4_LAND2") (pin "H2") (pinfunction "H2_H2") (pintype "passive"))
    )
    (net (code "136") (name "unconnected-(P4_LAND2-PadH3)") (class "Default")
      (node (ref "P4_LAND2") (pin "H3") (pinfunction "H3_H3") (pintype "passive"))
    )
    (net (code "137") (name "unconnected-(P4_LAND2-PadH4)") (class "Default")
      (node (ref "P4_LAND2") (pin "H4") (pinfunction "H4_H4") (pintype "passive"))
    )
    (net (code "138") (name "unconnected-(P4_LAND2-PadH5)") (class "Default")
      (node (ref "P4_LAND2") (pin "H5") (pinfunction "H5_H5") (pintype "passive"))
    )
    (net (code "139") (name "unconnected-(P4_LAND2-PadH6)") (class "Default")
      (node (ref "P4_LAND2") (pin "H6") (pinfunction "H6_H6") (pintype "passive"))
    )
    (net (code "140") (name "unconnected-(P4_LAND2-PadH7)") (class "Default")
      (node (ref "P4_LAND2") (pin "H7") (pinfunction "H7_H7") (pintype "passive"))
    )
    (net (code "141") (name "unconnected-(P4_LAND2-PadH8)") (class "Default")
      (node (ref "P4_LAND2") (pin "H8") (pinfunction "H8_H8") (pintype "passive"))
    )
    (net (code "142") (name "unconnected-(P4_LAND2-PadH9)") (class "Default")
      (node (ref "P4_LAND2") (pin "H9") (pinfunction "H9_H9") (pintype "passive"))
    )
    (net (code "143") (name "unconnected-(P4_LAND2-PadJ5)") (class "Default")
      (node (ref "P4_LAND2") (pin "J5") (pinfunction "J5_J5") (pintype "passive"))
    )
    (net (code "144") (name "unconnected-(P4_LAND2-PadJ6)") (class "Default")
      (node (ref "P4_LAND2") (pin "J6") (pinfunction "J6_J6") (pintype "passive"))
    )
    (net (code "145") (name "unconnected-(P4_LAND2-PadJ7)") (class "Default")
      (node (ref "P4_LAND2") (pin "J7") (pinfunction "J7_J7") (pintype "passive"))
    )
    (net (code "146") (name "unconnected-(P4_LAND2-PadJ8)") (class "Default")
      (node (ref "P4_LAND2") (pin "J8") (pinfunction "J8_J8") (pintype "passive"))
    )
    (net (code "147") (name "unconnected-(P4_LAND2-PadJ9)") (class "Default")
      (node (ref "P4_LAND2") (pin "J9") (pinfunction "J9_J9") (pintype "passive"))
    )
  )
)
